# eth.net
KiCad netlist of a schematic drawn in Altium Designer
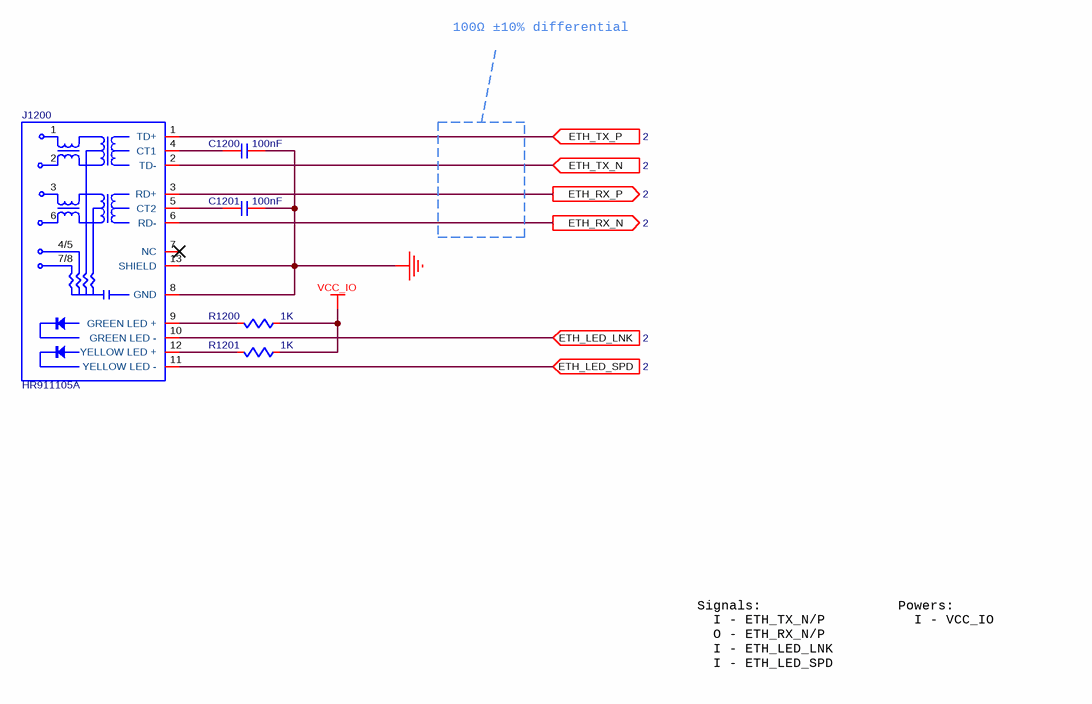
[diagram p0: eth.schdoc]

(export (version "E")
  (design (tool "Eeschema 10.0.6"))
  (components
    (comp (ref "C1200")
      (value "100nF")
      (footprint "mw:C0402")
      (fields (field (name "VOLTAGE") "50V") (field (name "Comment") "C-NOMO"))
      (libsource (lib "mw") (part "C-NOMO"))
    )
    (comp (ref "C1201")
      (value "100nF")
      (footprint "mw:C0402")
      (fields (field (name "VOLTAGE") "50V") (field (name "Comment") "C-NOMO"))
      (libsource (lib "mw") (part "C-NOMO"))
    )
    (comp (ref "J1200")
      (value "HR911105A")
      (footprint "mw:HR911105A")
      (description "RJ45 - 100Mbps, Mag, LED")
      (libsource (lib "mw") (part "HR911105A"))
    )
    (comp (ref "R1200")
      (value "1K")
      (footprint "mw:R0402")
      (fields (field (name "Comment") "R"))
      (libsource (lib "mw") (part "R"))
    )
    (comp (ref "R1201")
      (value "1K")
      (footprint "mw:R0402")
      (fields (field (name "Comment") "R"))
      (libsource (lib "mw") (part "R"))
    )
  )
  (nets
    (net (code "1") (name "/ETH_LED_LNK") (class "Default")
      (node (ref "J1200") (pin "10") (pinfunction "GREEN_LED_-_10") (pintype "passive"))
    )
    (net (code "2") (name "/ETH_LED_SPD") (class "Default")
      (node (ref "J1200") (pin "11") (pinfunction "YELLOW_LED_-_11") (pintype "passive"))
    )
    (net (code "3") (name "/ETH_RX_N") (class "Default")
      (node (ref "J1200") (pin "6") (pinfunction "RD-_6") (pintype "passive"))
    )
    (net (code "4") (name "/ETH_RX_P") (class "Default")
      (node (ref "J1200") (pin "3") (pinfunction "RD+_3") (pintype "passive"))
    )
    (net (code "5") (name "/ETH_TX_N") (class "Default")
      (node (ref "J1200") (pin "2") (pinfunction "TD-_2") (pintype "passive"))
    )
    (net (code "6") (name "/ETH_TX_P") (class "Default")
      (node (ref "J1200") (pin "1") (pinfunction "TD+_1") (pintype "passive"))
    )
    (net (code "7") (name "GND") (class "Default")
      (node (ref "C1200") (pin "1") (pinfunction "1_1") (pintype "passive"))
      (node (ref "C1201") (pin "1") (pinfunction "1_1") (pintype "passive"))
      (node (ref "J1200") (pin "13") (pinfunction "SHIELD_13") (pintype "passive"))
      (node (ref "J1200") (pin "8") (pinfunction "GND_8") (pintype "passive"))
    )
    (net (code "8") (name "Net-(J1200-CT1)") (class "Default")
      (node (ref "C1200") (pin "2") (pinfunction "2_2") (pintype "passive"))
      (node (ref "J1200") (pin "4") (pinfunction "CT1_4") (pintype "passive"))
    )
    (net (code "9") (name "Net-(J1200-CT2)") (class "Default")
      (node (ref "C1201") (pin "2") (pinfunction "2_2") (pintype "passive"))
      (node (ref "J1200") (pin "5") (pinfunction "CT2_5") (pintype "passive"))
    )
    (net (code "10") (name "Net-(J1200-GREEN_LED_+)") (class "Default")
      (node (ref "J1200") (pin "9") (pinfunction "GREEN_LED_+_9") (pintype "passive"))
      (node (ref "R1200") (pin "1") (pinfunction "1_1") (pintype "passive"))
    )
    (net (code "11") (name "Net-(J1200-YELLOW_LED_+)") (class "Default")
      (node (ref "J1200") (pin "12") (pinfunction "YELLOW_LED_+_12") (pintype "passive"))
      (node (ref "R1201") (pin "1") (pinfunction "1_1") (pintype "passive"))
    )
    (net (code "12") (name "VCC_IO") (class "Default")
      (node (ref "R1200") (pin "2") (pinfunction "2_2") (pintype "passive"))
      (node (ref "R1201") (pin "2") (pinfunction "2_2") (pintype "passive"))
    )
    (net (code "13") (name "unconnected-(J1200-NC-Pad7)") (class "Default")
      (node (ref "J1200") (pin "7") (pinfunction "NC_7") (pintype "passive+no_connect"))
    )
  )
)
